# slide-control-attiny85.net
KiCad netlist of a schematic drawn in EAGLE
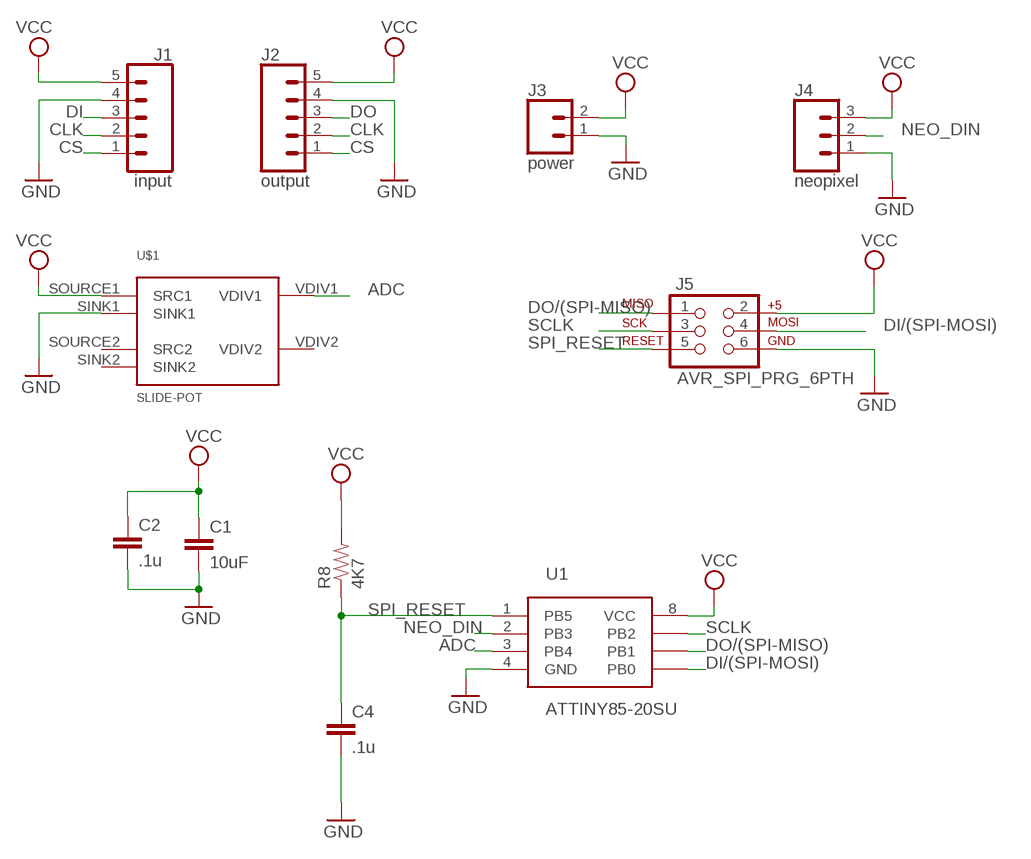
[diagram p0: schematic, sheet 1]

(export (version "E")
  (design (tool "Eeschema 10.0.6"))
  (components
    (comp (ref "C1")
      (value "10uF")
      (footprint "eagle-import:1206")
      (libsource (lib "eagle-import") (part "10UF-1206-6.3V-20%"))
    )
    (comp (ref "C2")
      (value ".1u")
      (footprint "eagle-import:0805")
      (libsource (lib "eagle-import") (part "CAP0805"))
    )
    (comp (ref "C4")
      (value ".1u")
      (footprint "eagle-import:0805")
      (libsource (lib "eagle-import") (part "CAP0805"))
    )
    (comp (ref "J1")
      (value "input")
      (footprint "eagle-import:1X05")
      (libsource (lib "eagle-import") (part "CONN_05"))
    )
    (comp (ref "J2")
      (value "output")
      (footprint "eagle-import:1X05")
      (libsource (lib "eagle-import") (part "CONN_05"))
    )
    (comp (ref "J3")
      (value "power")
      (footprint "eagle-import:1X02")
      (libsource (lib "eagle-import") (part "CONN_02"))
    )
    (comp (ref "J4")
      (value "neopixel")
      (footprint "eagle-import:1X03")
      (libsource (lib "eagle-import") (part "CONN_03"))
    )
    (comp (ref "J5")
      (value "AVR_SPI_PRG_6PTH")
      (footprint "eagle-import:2X3")
      (libsource (lib "eagle-import") (part "AVR_SPI_PRG_6PTH"))
    )
    (comp (ref "R8")
      (value "4K7")
      (footprint "eagle-import:0805")
      (libsource (lib "eagle-import") (part "RESISTOR"))
    )
    (comp (ref "U$1")
      (value "SLIDE-POT")
      (footprint "eagle-import:SLIDE-POT")
      (libsource (lib "eagle-import") (part "SLIDE-POT"))
    )
    (comp (ref "U1")
      (value "ATTINY85-20SU")
      (footprint "eagle-import:SOIC-8")
      (fields
        (field (name "DIGI_KEY_PART_NUMBER") "ATTINY85-20SU-ND")
        (field (name "MANUFACTURER") "Microchip Technology")
        (field (name "CREATED_BY") "PCBLayout.com")
      )
      (libsource (lib "eagle-import") (part "ATTINY85-20SU"))
    )
  )
  (nets
    (net (code "1") (name "/ADC") (class "Default")
      (node (ref "U$1") (pin "VDIV1") (pinfunction "VDIV1_VDIV1") (pintype "bidirectional"))
      (node (ref "U1") (pin "3") (pinfunction "PB4_3") (pintype "bidirectional"))
    )
    (net (code "2") (name "/CLK") (class "Default")
      (node (ref "J1") (pin "2") (pinfunction "2_2") (pintype "passive"))
      (node (ref "J2") (pin "2") (pinfunction "2_2") (pintype "passive"))
    )
    (net (code "3") (name "/CS") (class "Default")
      (node (ref "J1") (pin "1") (pinfunction "1_1") (pintype "passive"))
      (node (ref "J2") (pin "1") (pinfunction "1_1") (pintype "passive"))
    )
    (net (code "4") (name "/DI") (class "Default")
      (node (ref "J1") (pin "3") (pinfunction "3_3") (pintype "passive"))
    )
    (net (code "5") (name "/DI{slash}(SPI-MOSI)") (class "Default")
      (node (ref "J5") (pin "4") (pinfunction "4_4") (pintype "passive"))
      (node (ref "U1") (pin "5") (pinfunction "PB0_5") (pintype "bidirectional"))
    )
    (net (code "6") (name "/DO") (class "Default")
      (node (ref "J2") (pin "3") (pinfunction "3_3") (pintype "passive"))
    )
    (net (code "7") (name "/DO{slash}(SPI-MISO)") (class "Default")
      (node (ref "J5") (pin "1") (pinfunction "1_1") (pintype "passive"))
      (node (ref "U1") (pin "6") (pinfunction "PB1_6") (pintype "bidirectional"))
    )
    (net (code "8") (name "/NEO_DIN") (class "Default")
      (node (ref "J4") (pin "2") (pinfunction "2_2") (pintype "passive"))
      (node (ref "U1") (pin "2") (pinfunction "PB3_2") (pintype "bidirectional"))
    )
    (net (code "9") (name "/SCLK") (class "Default")
      (node (ref "J5") (pin "3") (pinfunction "3_3") (pintype "passive"))
      (node (ref "U1") (pin "7") (pinfunction "PB2_7") (pintype "bidirectional"))
    )
    (net (code "10") (name "/SPI_RESET") (class "Default")
      (node (ref "C4") (pin "1") (pinfunction "1_1") (pintype "passive"))
      (node (ref "J5") (pin "5") (pinfunction "5_5") (pintype "passive"))
      (node (ref "R8") (pin "1") (pinfunction "1_1") (pintype "passive"))
      (node (ref "U1") (pin "1") (pinfunction "PB5_1") (pintype "bidirectional"))
    )
    (net (code "11") (name "GND") (class "Default")
      (node (ref "C1") (pin "2") (pinfunction "2_2") (pintype "passive"))
      (node (ref "C2") (pin "2") (pinfunction "2_2") (pintype "passive"))
      (node (ref "C4") (pin "2") (pinfunction "2_2") (pintype "passive"))
      (node (ref "J1") (pin "4") (pinfunction "4_4") (pintype "passive"))
      (node (ref "J2") (pin "4") (pinfunction "4_4") (pintype "passive"))
      (node (ref "J3") (pin "1") (pinfunction "1_1") (pintype "passive"))
      (node (ref "J4") (pin "1") (pinfunction "1_1") (pintype "passive"))
      (node (ref "J5") (pin "6") (pinfunction "6_6") (pintype "passive"))
      (node (ref "U$1") (pin "SINK1") (pinfunction "SINK1_SINK1") (pintype "bidirectional"))
      (node (ref "U1") (pin "4") (pinfunction "GND_4") (pintype "power_in"))
    )
    (net (code "12") (name "VCC") (class "Default")
      (node (ref "C1") (pin "1") (pinfunction "1_1") (pintype "passive"))
      (node (ref "C2") (pin "1") (pinfunction "1_1") (pintype "passive"))
      (node (ref "J1") (pin "5") (pinfunction "5_5") (pintype "passive"))
      (node (ref "J2") (pin "5") (pinfunction "5_5") (pintype "passive"))
      (node (ref "J3") (pin "2") (pinfunction "2_2") (pintype "passive"))
      (node (ref "J4") (pin "3") (pinfunction "3_3") (pintype "passive"))
      (node (ref "J5") (pin "2") (pinfunction "2_2") (pintype "passive"))
      (node (ref "R8") (pin "2") (pinfunction "2_2") (pintype "passive"))
      (node (ref "U$1") (pin "SOURCE1") (pinfunction "SRC1_SOURCE1") (pintype "bidirectional"))
      (node (ref "U1") (pin "8") (pinfunction "VCC_8") (pintype "power_in"))
    )
    (net (code "13") (name "unconnected-(U$1-PadSINK2)") (class "Default")
      (node (ref "U$1") (pin "SINK2") (pinfunction "SINK2_SINK2") (pintype "bidirectional"))
    )
    (net (code "14") (name "unconnected-(U$1-PadVDIV2)") (class "Default")
      (node (ref "U$1") (pin "VDIV2") (pinfunction "VDIV2_VDIV2") (pintype "bidirectional"))
    )
    (net (code "15") (name "unconnected-(U$1-SRC2-PadSOURCE2)") (class "Default")
      (node (ref "U$1") (pin "SOURCE2") (pinfunction "SRC2_SOURCE2") (pintype "bidirectional"))
    )
  )
)
